# ETHNET.net
KiCad netlist of a schematic drawn in Altium Designer
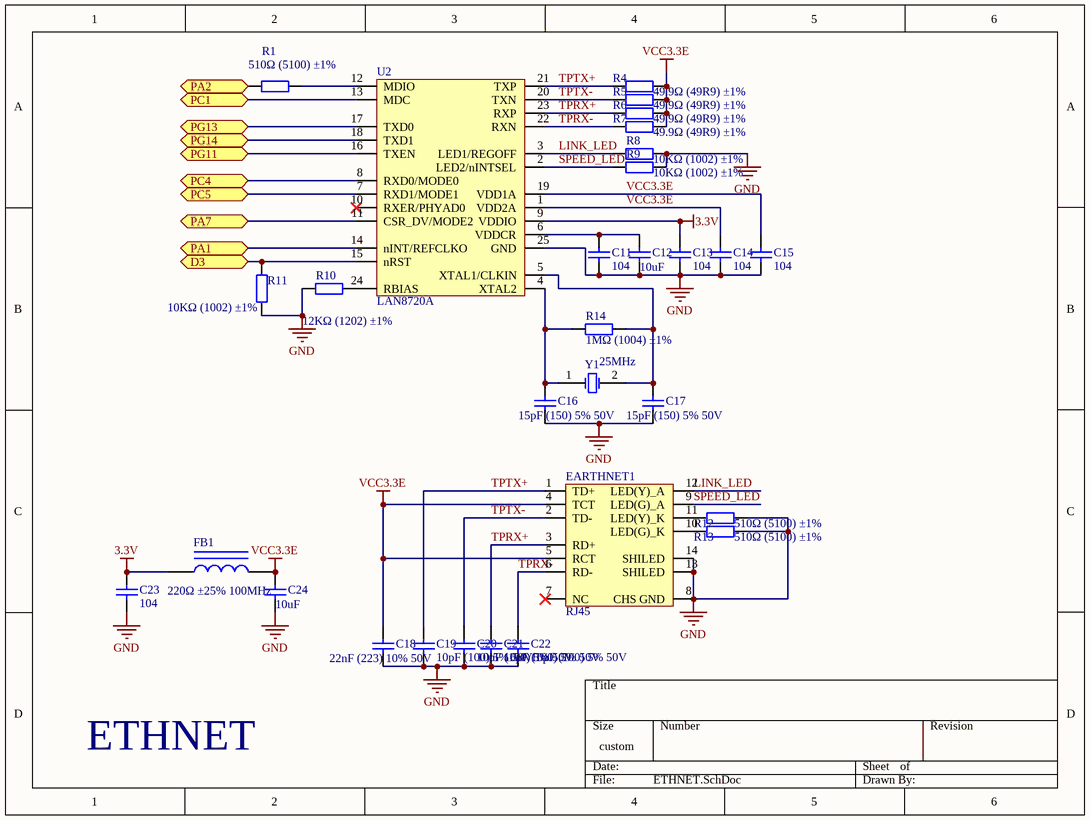
[diagram p0: ETHNET.SchDoc]

(export (version "E")
  (design (tool "Eeschema 10.0.6"))
  (components
    (comp (ref "C11")
      (value "104")
      (footprint "0805_C")
      (description "贴片电容")
      (libsource (lib "Cap") (part "0805 100nF(104) 10% 50V"))
    )
    (comp (ref "C12")
      (value "10uF")
      (footprint "0805_C")
      (description "贴片电容")
      (libsource (lib "Cap") (part "0805 100nF(104) 10% 50V"))
    )
    (comp (ref "C13")
      (value "104")
      (footprint "0805_C")
      (description "贴片电容")
      (libsource (lib "Cap") (part "0805 100nF(104) 10% 50V"))
    )
    (comp (ref "C14")
      (value "104")
      (footprint "0805_C")
      (description "贴片电容")
      (libsource (lib "Cap") (part "0805 100nF(104) 10% 50V"))
    )
    (comp (ref "C15")
      (value "104")
      (footprint "0805_C")
      (description "贴片电容")
      (libsource (lib "Cap") (part "0805 100nF(104) 10% 50V"))
    )
    (comp (ref "C16")
      (value "15pF (150) 5% 50V")
      (footprint "0805_C")
      (description "贴片电容")
      (libsource (lib "Cap") (part "0805 15pF (150) 5% 50V"))
    )
    (comp (ref "C17")
      (value "15pF (150) 5% 50V")
      (footprint "0805_C")
      (description "贴片电容")
      (libsource (lib "Cap") (part "0805 15pF (150) 5% 50V"))
    )
    (comp (ref "C18")
      (value "22nF (223) 10% 50V")
      (footprint "0805_C")
      (description "贴片电容")
      (libsource (lib "Cap") (part "0805 22nF (223) 10% 50V"))
    )
    (comp (ref "C19")
      (value "10pF (100) 5% 50V")
      (footprint "0805_C")
      (description "贴片电容")
      (libsource (lib "Cap") (part "0805 10pF (100) 5% 50V"))
    )
    (comp (ref "C20")
      (value "10pF (100) 5% 50V")
      (footprint "0805_C")
      (description "贴片电容")
      (libsource (lib "Cap") (part "0805 10pF (100) 5% 50V"))
    )
    (comp (ref "C21")
      (value "10pF (100) 5% 50V")
      (footprint "0805_C")
      (description "贴片电容")
      (libsource (lib "Cap") (part "0805 10pF (100) 5% 50V"))
    )
    (comp (ref "C22")
      (value "10pF (100) 5% 50V")
      (footprint "0805_C")
      (description "贴片电容")
      (libsource (lib "Cap") (part "0805 10pF (100) 5% 50V"))
    )
    (comp (ref "C23")
      (value "104")
      (footprint "0805_C")
      (description "贴片电容")
      (libsource (lib "Cap") (part "0805 100nF(104) 10% 50V"))
    )
    (comp (ref "C24")
      (value "10uF")
      (footprint "0805_C")
      (description "贴片电容")
      (libsource (lib "Cap") (part "0805 100nF(104) 10% 50V"))
    )
    (comp (ref "EARTHNET1")
      (value "RJ45")
      (footprint "HR911105A")
      (libsource (lib "EXPLORER") (part "HR911105"))
    )
    (comp (ref "FB1")
      (value "220Ω ±25% 100MHz")
      (footprint "0805_L")
      (description "贴片磁珠")
      (libsource (lib "IUD") (part "0805 100Ω 25% 100MHz"))
    )
    (comp (ref "R1")
      (value "510Ω (5100) ±1%")
      (footprint "0805_R")
      (description "贴片电阻")
      (libsource (lib "") (part "0805 510Ω (5100) 1%_1"))
    )
    (comp (ref "R4")
      (value "49.9Ω (49R9) ±1%")
      (footprint "0805_R")
      (description "贴片电阻")
      (libsource (lib "RES") (part "0805 49.9Ω (49R9) 1%"))
    )
    (comp (ref "R5")
      (value "49.9Ω (49R9) ±1%")
      (footprint "0805_R")
      (description "贴片电阻")
      (libsource (lib "RES") (part "0805 49.9Ω (49R9) 1%"))
    )
    (comp (ref "R6")
      (value "49.9Ω (49R9) ±1%")
      (footprint "0805_R")
      (description "贴片电阻")
      (libsource (lib "RES") (part "0805 49.9Ω (49R9) 1%"))
    )
    (comp (ref "R7")
      (value "49.9Ω (49R9) ±1%")
      (footprint "0805_R")
      (description "贴片电阻")
      (libsource (lib "RES") (part "0805 49.9Ω (49R9) 1%"))
    )
    (comp (ref "R8")
      (value "10KΩ (1002) ±1%")
      (footprint "0805_R")
      (description "贴片电阻")
      (libsource (lib "RES") (part "0805 10KΩ (1002) 1%"))
    )
    (comp (ref "R9")
      (value "10KΩ (1002) ±1%")
      (footprint "0805_R")
      (description "贴片电阻")
      (libsource (lib "RES") (part "0805 10KΩ (1002) 1%"))
    )
    (comp (ref "R10")
      (value "12KΩ (1202) ±1%")
      (footprint "0805_R")
      (description "贴片电阻")
      (libsource (lib "RES") (part "0805 12KΩ (1202) 1%"))
    )
    (comp (ref "R11")
      (value "10KΩ (1002) ±1%")
      (footprint "0805_R")
      (description "贴片电阻")
      (libsource (lib "") (part "0805 10KΩ (1002) 1%_1"))
    )
    (comp (ref "R12")
      (value "510Ω (5100) ±1%")
      (footprint "0805_R")
      (description "贴片电阻")
      (libsource (lib "RES") (part "0805 510Ω (5100) 1%"))
    )
    (comp (ref "R13")
      (value "510Ω (5100) ±1%")
      (footprint "0805_R")
      (description "贴片电阻")
      (libsource (lib "RES") (part "0805 510Ω (5100) 1%"))
    )
    (comp (ref "R14")
      (value "1MΩ (1004) ±1%")
      (footprint "0805_R")
      (description "贴片电阻")
      (libsource (lib "RES") (part "0805 1MΩ (1004) 1%"))
    )
    (comp (ref "U2")
      (value "LAN8720A")
      (footprint "QFN24")
      (description "ETH PHY")
      (libsource (lib "EXPLORER") (part "LAN8720"))
    )
    (comp (ref "Y1")
      (value "25MHz")
      (footprint "XTAL_US")
      (description "Crystal Oscillator")
      (fields (field (name "PUBLISHER") "Altium Limited"))
      (libsource (lib "EXPLORER") (part "XTAL"))
    )
  )
  (nets
    (net (code "1") (name "/D3") (class "Default")
      (node (ref "R11") (pin "2") (pinfunction "2_2") (pintype "passive"))
      (node (ref "U2") (pin "15") (pinfunction "nRST_15") (pintype "passive"))
    )
    (net (code "2") (name "/LINK_LED") (class "Default")
      (node (ref "EARTHNET1") (pin "12") (pinfunction "LED(Y)_A_12") (pintype "passive"))
      (node (ref "R8") (pin "1") (pinfunction "1_1") (pintype "passive"))
      (node (ref "U2") (pin "3") (pinfunction "LED1/REGOFF_3") (pintype "passive"))
    )
    (net (code "3") (name "/PA1") (class "Default")
      (node (ref "U2") (pin "14") (pinfunction "nINT/REFCLKO_14") (pintype "passive"))
    )
    (net (code "4") (name "/PA2") (class "Default")
      (node (ref "R1") (pin "1") (pinfunction "1_1") (pintype "passive"))
    )
    (net (code "5") (name "/PA7") (class "Default")
      (node (ref "U2") (pin "11") (pinfunction "CSR_DV/MODE2_11") (pintype "passive"))
    )
    (net (code "6") (name "/PC1") (class "Default")
      (node (ref "U2") (pin "13") (pinfunction "MDC_13") (pintype "passive"))
    )
    (net (code "7") (name "/PC4") (class "Default")
      (node (ref "U2") (pin "8") (pinfunction "RXD0/MODE0_8") (pintype "passive"))
    )
    (net (code "8") (name "/PC5") (class "Default")
      (node (ref "U2") (pin "7") (pinfunction "RXD1/MODE1_7") (pintype "passive"))
    )
    (net (code "9") (name "/PG11") (class "Default")
      (node (ref "U2") (pin "16") (pinfunction "TXEN_16") (pintype "passive"))
    )
    (net (code "10") (name "/PG13") (class "Default")
      (node (ref "U2") (pin "17") (pinfunction "TXD0_17") (pintype "passive"))
    )
    (net (code "11") (name "/PG14") (class "Default")
      (node (ref "U2") (pin "18") (pinfunction "TXD1_18") (pintype "passive"))
    )
    (net (code "12") (name "/SPEED_LED") (class "Default")
      (node (ref "EARTHNET1") (pin "9") (pinfunction "LED(G)_A_9") (pintype "passive"))
      (node (ref "R9") (pin "1") (pinfunction "1_1") (pintype "passive"))
      (node (ref "U2") (pin "2") (pinfunction "LED2/nINTSEL_2") (pintype "passive"))
    )
    (net (code "13") (name "/TPRX+") (class "Default")
      (node (ref "C21") (pin "2") (pinfunction "2_2") (pintype "passive"))
      (node (ref "EARTHNET1") (pin "3") (pinfunction "RD+_3") (pintype "passive"))
      (node (ref "R6") (pin "1") (pinfunction "1_1") (pintype "passive"))
      (node (ref "U2") (pin "23") (pinfunction "RXP_23") (pintype "passive"))
    )
    (net (code "14") (name "/TPRX-") (class "Default")
      (node (ref "C22") (pin "2") (pinfunction "2_2") (pintype "passive"))
      (node (ref "EARTHNET1") (pin "6") (pinfunction "RD-_6") (pintype "passive"))
      (node (ref "R7") (pin "1") (pinfunction "1_1") (pintype "passive"))
      (node (ref "U2") (pin "22") (pinfunction "RXN_22") (pintype "passive"))
    )
    (net (code "15") (name "/TPTX+") (class "Default")
      (node (ref "C19") (pin "2") (pinfunction "2_2") (pintype "passive"))
      (node (ref "EARTHNET1") (pin "1") (pinfunction "TD+_1") (pintype "passive"))
      (node (ref "R4") (pin "1") (pinfunction "1_1") (pintype "passive"))
      (node (ref "U2") (pin "21") (pinfunction "TXP_21") (pintype "passive"))
    )
    (net (code "16") (name "/TPTX-") (class "Default")
      (node (ref "C20") (pin "2") (pinfunction "2_2") (pintype "passive"))
      (node (ref "EARTHNET1") (pin "2") (pinfunction "TD-_2") (pintype "passive"))
      (node (ref "R5") (pin "1") (pinfunction "1_1") (pintype "passive"))
      (node (ref "U2") (pin "20") (pinfunction "TXN_20") (pintype "passive"))
    )
    (net (code "17") (name "3.3V") (class "Default")
      (node (ref "C13") (pin "2") (pinfunction "2_2") (pintype "passive"))
      (node (ref "C23") (pin "2") (pinfunction "2_2") (pintype "passive"))
      (node (ref "FB1") (pin "1") (pinfunction "1_1") (pintype "passive"))
      (node (ref "U2") (pin "9") (pinfunction "VDDIO_9") (pintype "passive"))
    )
    (net (code "18") (name "GND") (class "Default")
      (node (ref "C11") (pin "1") (pinfunction "1_1") (pintype "passive"))
      (node (ref "C12") (pin "1") (pinfunction "1_1") (pintype "passive"))
      (node (ref "C13") (pin "1") (pinfunction "1_1") (pintype "passive"))
      (node (ref "C14") (pin "1") (pinfunction "1_1") (pintype "passive"))
      (node (ref "C15") (pin "1") (pinfunction "1_1") (pintype "passive"))
      (node (ref "C16") (pin "1") (pinfunction "1_1") (pintype "passive"))
      (node (ref "C17") (pin "1") (pinfunction "1_1") (pintype "passive"))
      (node (ref "C18") (pin "1") (pinfunction "1_1") (pintype "passive"))
      (node (ref "C19") (pin "1") (pinfunction "1_1") (pintype "passive"))
      (node (ref "C20") (pin "1") (pinfunction "1_1") (pintype "passive"))
      (node (ref "C21") (pin "1") (pinfunction "1_1") (pintype "passive"))
      (node (ref "C22") (pin "1") (pinfunction "1_1") (pintype "passive"))
      (node (ref "C23") (pin "1") (pinfunction "1_1") (pintype "passive"))
      (node (ref "C24") (pin "1") (pinfunction "1_1") (pintype "passive"))
      (node (ref "EARTHNET1") (pin "13") (pinfunction "SHILED_13") (pintype "passive"))
      (node (ref "EARTHNET1") (pin "14") (pinfunction "SHILED_14") (pintype "passive"))
      (node (ref "EARTHNET1") (pin "8") (pinfunction "CHS_GND_8") (pintype "passive"))
      (node (ref "R10") (pin "1") (pinfunction "1_1") (pintype "passive"))
      (node (ref "R11") (pin "1") (pinfunction "1_1") (pintype "passive"))
      (node (ref "R12") (pin "1") (pinfunction "1_1") (pintype "passive"))
      (node (ref "R13") (pin "1") (pinfunction "1_1") (pintype "passive"))
      (node (ref "R8") (pin "2") (pinfunction "2_2") (pintype "passive"))
      (node (ref "R9") (pin "2") (pinfunction "2_2") (pintype "passive"))
      (node (ref "U2") (pin "25") (pinfunction "GND_25") (pintype "passive"))
    )
    (net (code "19") (name "Net-(EARTHNET1-LED(G)_K)") (class "Default")
      (node (ref "EARTHNET1") (pin "10") (pinfunction "LED(G)_K_10") (pintype "passive"))
      (node (ref "R13") (pin "2") (pinfunction "2_2") (pintype "passive"))
    )
    (net (code "20") (name "Net-(EARTHNET1-LED(Y)_K)") (class "Default")
      (node (ref "EARTHNET1") (pin "11") (pinfunction "LED(Y)_K_11") (pintype "passive"))
      (node (ref "R12") (pin "2") (pinfunction "2_2") (pintype "passive"))
    )
    (net (code "21") (name "Net-(U2-MDIO)") (class "Default")
      (node (ref "R1") (pin "2") (pinfunction "2_2") (pintype "passive"))
      (node (ref "U2") (pin "12") (pinfunction "MDIO_12") (pintype "passive"))
    )
    (net (code "22") (name "Net-(U2-RBIAS)") (class "Default")
      (node (ref "R10") (pin "2") (pinfunction "2_2") (pintype "passive"))
      (node (ref "U2") (pin "24") (pinfunction "RBIAS_24") (pintype "passive"))
    )
    (net (code "23") (name "Net-(U2-VDDCR)") (class "Default")
      (node (ref "C11") (pin "2") (pinfunction "2_2") (pintype "passive"))
      (node (ref "C12") (pin "2") (pinfunction "2_2") (pintype "passive"))
      (node (ref "U2") (pin "6") (pinfunction "VDDCR_6") (pintype "passive"))
    )
    (net (code "24") (name "Net-(U2-XTAL1{slash}CLKIN)") (class "Default")
      (node (ref "C17") (pin "2") (pinfunction "2_2") (pintype "passive"))
      (node (ref "R14") (pin "2") (pinfunction "2_2") (pintype "passive"))
      (node (ref "U2") (pin "5") (pinfunction "XTAL1/CLKIN_5") (pintype "passive"))
      (node (ref "Y1") (pin "2") (pinfunction "OSC2_2") (pintype "passive"))
    )
    (net (code "25") (name "Net-(U2-XTAL2)") (class "Default")
      (node (ref "C16") (pin "2") (pinfunction "2_2") (pintype "passive"))
      (node (ref "R14") (pin "1") (pinfunction "1_1") (pintype "passive"))
      (node (ref "U2") (pin "4") (pinfunction "XTAL2_4") (pintype "passive"))
      (node (ref "Y1") (pin "1") (pinfunction "OSC1_1") (pintype "passive"))
    )
    (net (code "26") (name "VCC3.3E") (class "Default")
      (node (ref "C14") (pin "2") (pinfunction "2_2") (pintype "passive"))
      (node (ref "C15") (pin "2") (pinfunction "2_2") (pintype "passive"))
      (node (ref "C18") (pin "2") (pinfunction "2_2") (pintype "passive"))
      (node (ref "C24") (pin "2") (pinfunction "2_2") (pintype "passive"))
      (node (ref "EARTHNET1") (pin "4") (pinfunction "TCT_4") (pintype "passive"))
      (node (ref "EARTHNET1") (pin "5") (pinfunction "RCT_5") (pintype "passive"))
      (node (ref "FB1") (pin "2") (pinfunction "2_2") (pintype "passive"))
      (node (ref "R4") (pin "2") (pinfunction "2_2") (pintype "passive"))
      (node (ref "R5") (pin "2") (pinfunction "2_2") (pintype "passive"))
      (node (ref "R6") (pin "2") (pinfunction "2_2") (pintype "passive"))
      (node (ref "R7") (pin "2") (pinfunction "2_2") (pintype "passive"))
      (node (ref "U2") (pin "1") (pinfunction "VDD2A_1") (pintype "passive"))
      (node (ref "U2") (pin "19") (pinfunction "VDD1A_19") (pintype "passive"))
    )
    (net (code "27") (name "unconnected-(EARTHNET1-NC-Pad7)") (class "Default")
      (node (ref "EARTHNET1") (pin "7") (pinfunction "NC_7") (pintype "passive+no_connect"))
    )
    (net (code "28") (name "unconnected-(U2-RXER{slash}PHYAD0-Pad10)") (class "Default")
      (node (ref "U2") (pin "10") (pinfunction "RXER/PHYAD0_10") (pintype "passive+no_connect"))
    )
  )
)
